# 09_Expansion_Connect.net
KiCad netlist of a schematic drawn in Altium Designer
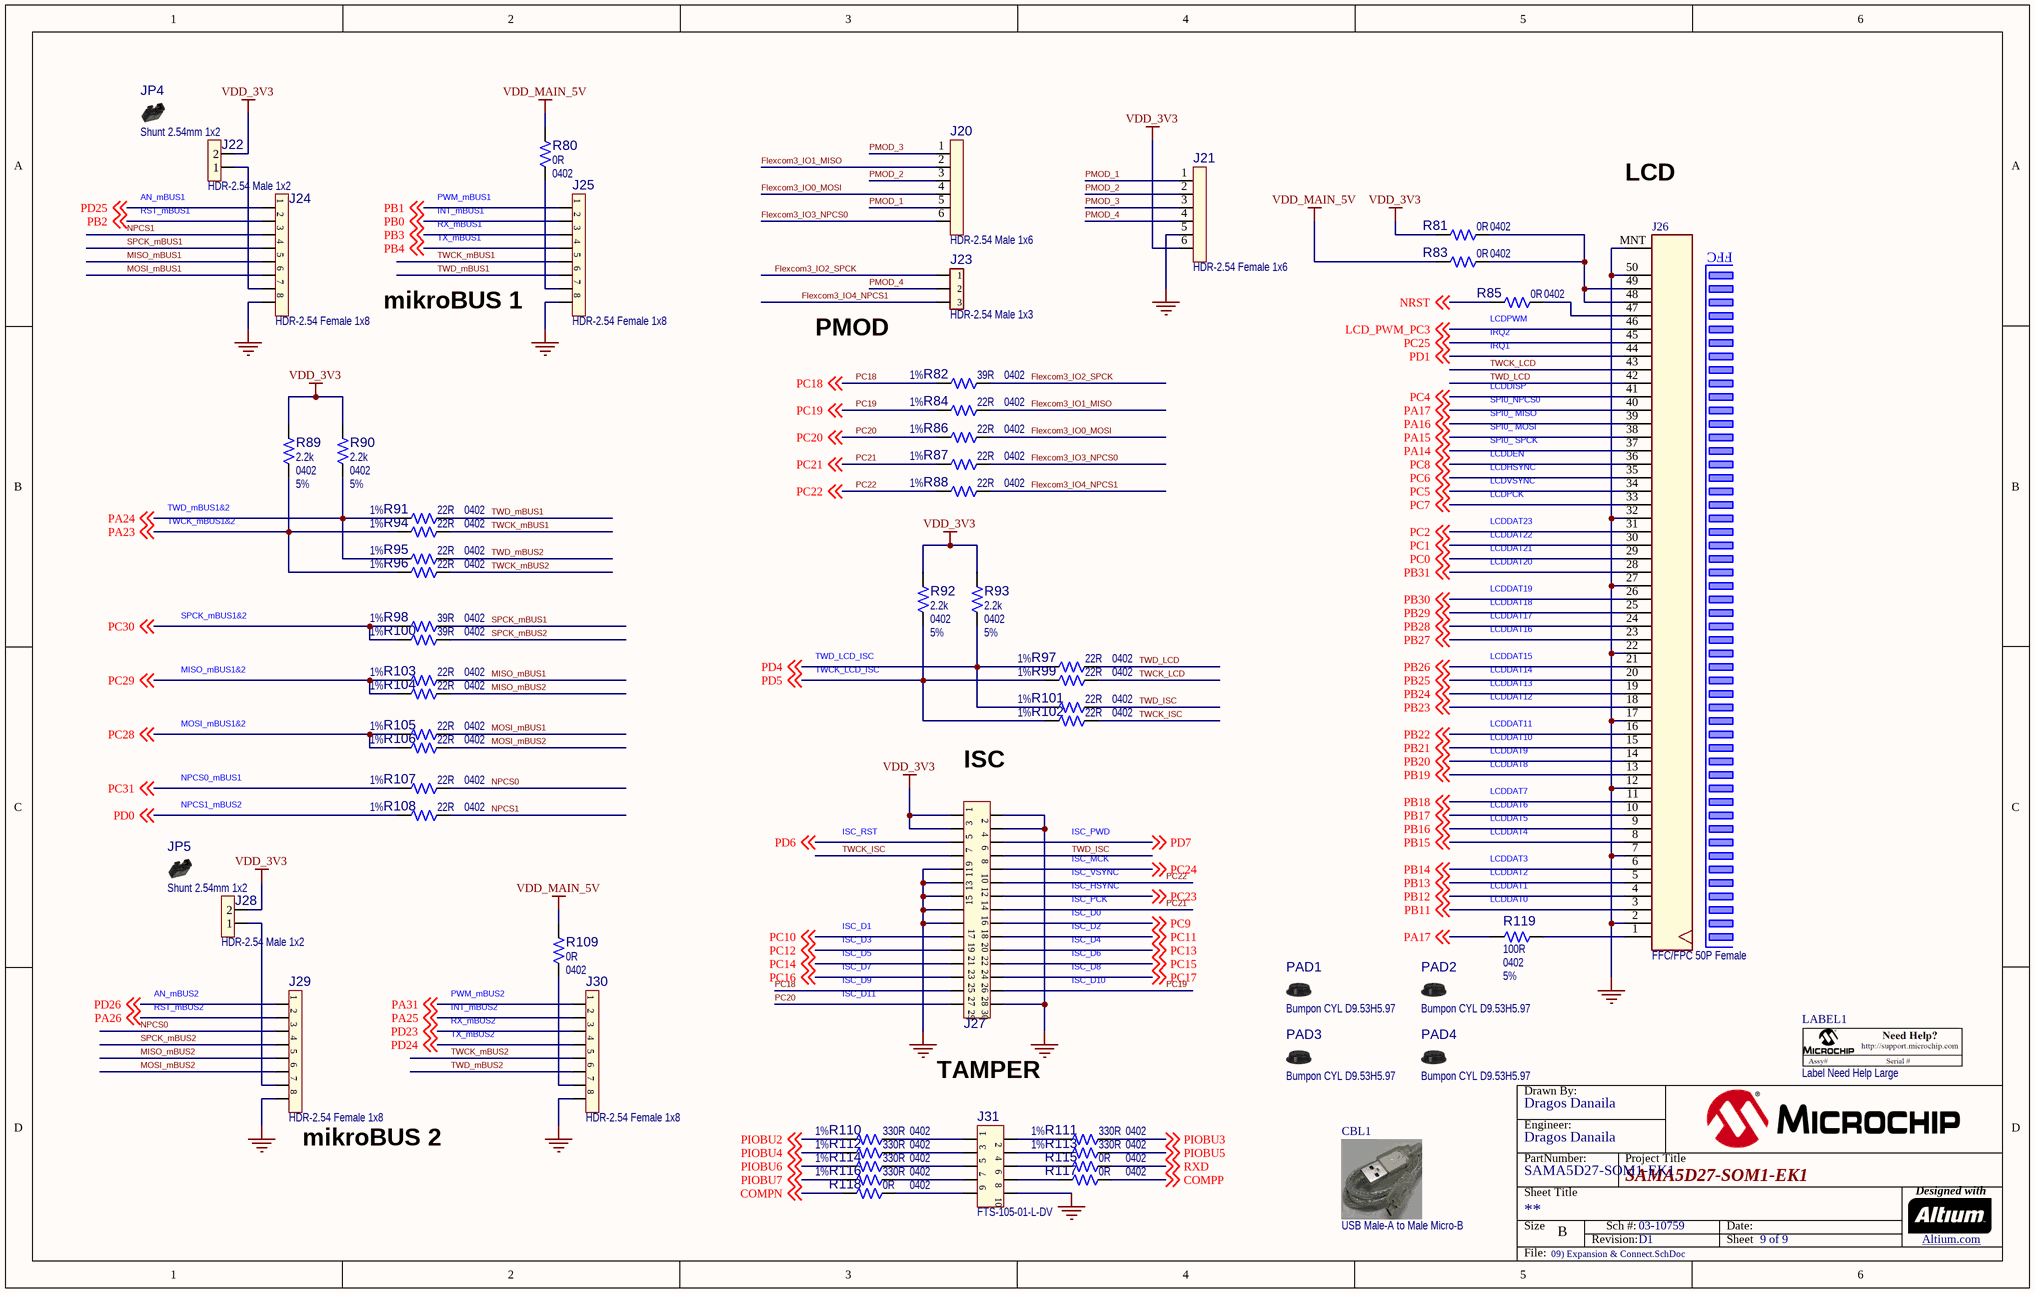
[diagram p0: 09) Expansion & Connect.SchDoc]

(export (version "E")
  (design (tool "Eeschema 10.0.6"))
  (components
    (comp (ref "CBL1")
      (value "USB Male-A to Male Micro-B")
      (fields (field (name "Comment") "Cable USB A to Micro-B"))
      (libsource (lib "MCHP-CDB") (part "Cable USB A to Micro-B"))
    )
    (comp (ref "J20")
      (value "HDR-2.54 Male 1x6")
      (footprint "HDR_M_2.54_1x6")
      (fields (field (name "Comment") "Header 1x6") (field (name "OWNER") "Bogdan P (M91398)"))
      (libsource (lib "MCHP-CDB") (part "Header 1x6"))
    )
    (comp (ref "J21")
      (value "HDR-2.54 Female 1x6")
      (footprint "HDR_F_2.54_1x6_RA")
      (fields (field (name "Comment") "Header 1x6"))
      (libsource (lib "MCHP-CDB") (part "Header 1x6"))
    )
    (comp (ref "J22")
      (value "HDR-2.54 Male 1x2")
      (footprint "HDR_M_2.54_1x2")
      (fields (field (name "Comment") "Header 1x2") (field (name "OWNER") "Bogdan P (M91398)"))
      (libsource (lib "MCHP-CDB") (part "Header 1x2"))
    )
    (comp (ref "J23")
      (value "HDR-2.54 Male 1x3")
      (footprint "HDR_M_2.54_1x3")
      (fields (field (name "Comment") "Header 1x3") (field (name "OWNER") "Bogdan P (M91398)"))
      (libsource (lib "MCHP-CDB") (part "Header 1x3"))
    )
    (comp (ref "J24")
      (value "HDR-2.54 Female 1x8")
      (footprint "HDR_F_2.54_1X8")
      (description "CON HDR-2.54 Female 1x8 Gold TH")
      (fields (field (name "Comment") "Header 1x8") (field (name "OWNER") "Jamus Griego"))
      (libsource (lib "MCHP-CDB") (part "Header 1x8"))
    )
    (comp (ref "J25")
      (value "HDR-2.54 Female 1x8")
      (footprint "HDR_F_2.54_1X8")
      (description "CON HDR-2.54 Female 1x8 Gold TH")
      (fields (field (name "Comment") "Header 1x8") (field (name "OWNER") "Jamus Griego"))
      (libsource (lib "MCHP-CDB") (part "Header 1x8"))
    )
    (comp (ref "J26")
      (value "FFC/FPC 50P Female")
      (footprint "CON_FFC_0.5_FEMALE_1X50_SMD_OMR_XF2M-5015-1A")
      (fields (field (name "Comment") "CON FFC 1x50 Mount") (field (name "OWNER") "Tad Ahlvers"))
      (libsource (lib "MCHP-CDB") (part "CON FFC 1x50 Mount"))
    )
    (comp (ref "J27")
      (value "Header 2x15")
      (footprint "HDR_M_2.54_2x15")
      (fields (field (name "OWNER") "Tim Moffat"))
      (libsource (lib "MCHP-CDB") (part "Header 2x15"))
    )
    (comp (ref "J28")
      (value "HDR-2.54 Male 1x2")
      (footprint "HDR_M_2.54_1x2")
      (fields (field (name "Comment") "Header 1x2") (field (name "OWNER") "Bogdan P (M91398)"))
      (libsource (lib "MCHP-CDB") (part "Header 1x2"))
    )
    (comp (ref "J29")
      (value "HDR-2.54 Female 1x8")
      (footprint "HDR_F_2.54_1X8")
      (description "CON HDR-2.54 Female 1x8 Gold TH")
      (fields (field (name "Comment") "Header 1x8") (field (name "OWNER") "Jamus Griego"))
      (libsource (lib "MCHP-CDB") (part "Header 1x8"))
    )
    (comp (ref "J30")
      (value "HDR-2.54 Female 1x8")
      (footprint "HDR_F_2.54_1X8")
      (description "CON HDR-2.54 Female 1x8 Gold TH")
      (fields (field (name "Comment") "Header 1x8") (field (name "OWNER") "Jamus Griego"))
      (libsource (lib "MCHP-CDB") (part "Header 1x8"))
    )
    (comp (ref "J31")
      (value "FTS-105-01-L-DV")
      (footprint "HDR_M_1.27_2x5_SMD_V_SAM_FTS-105-01-L-DV")
      (fields (field (name "Comment") "Header 2x5") (field (name "OWNER") "Dragos Danaila"))
      (libsource (lib "MCHP-CDB") (part "Header 2x5"))
    )
    (comp (ref "JP4")
      (value "Shunt 2.54mm 1x2")
      (footprint "Jumper_Mechanical")
      (fields (field (name "Comment") "Jumper Mechanical") (field (name "OWNER") "Mike Ragsdale"))
      (libsource (lib "MCHP-CDB") (part "Jumper Mechanical"))
    )
    (comp (ref "JP5")
      (value "Shunt 2.54mm 1x2")
      (footprint "Jumper_Mechanical")
      (fields (field (name "Comment") "Jumper Mechanical") (field (name "OWNER") "Mike Ragsdale"))
      (libsource (lib "MCHP-CDB") (part "Jumper Mechanical"))
    )
    (comp (ref "LABEL1")
      (value "Label Need Help Large")
      (footprint "LABEL_Need_Help_Large")
      (fields (field (name "Comment") "LABEL_Need_Help_Large"))
      (libsource (lib "MCHP-CDB") (part "LABEL_Need_Help_Large"))
    )
    (comp (ref "PAD1")
      (value "Bumpon CYL D9.53H5.97")
      (footprint "BUMP_3M_SJ61A2_CYLINDRICAL_BLACK_D9.53H5.97")
      (fields (field (name "Comment") "Rubber Pad Cylindrical") (field (name "OWNER") "Mark Loper"))
      (libsource (lib "MCHP-CDB") (part "Rubber Pad Cylindrical"))
    )
    (comp (ref "PAD2")
      (value "Bumpon CYL D9.53H5.97")
      (footprint "BUMP_3M_SJ61A2_CYLINDRICAL_BLACK_D9.53H5.97")
      (fields (field (name "Comment") "Rubber Pad Cylindrical") (field (name "OWNER") "Mark Loper"))
      (libsource (lib "MCHP-CDB") (part "Rubber Pad Cylindrical"))
    )
    (comp (ref "PAD3")
      (value "Bumpon CYL D9.53H5.97")
      (footprint "BUMP_3M_SJ61A2_CYLINDRICAL_BLACK_D9.53H5.97")
      (fields (field (name "Comment") "Rubber Pad Cylindrical") (field (name "OWNER") "Mark Loper"))
      (libsource (lib "MCHP-CDB") (part "Rubber Pad Cylindrical"))
    )
    (comp (ref "PAD4")
      (value "Bumpon CYL D9.53H5.97")
      (footprint "BUMP_3M_SJ61A2_CYLINDRICAL_BLACK_D9.53H5.97")
      (fields (field (name "Comment") "Rubber Pad Cylindrical") (field (name "OWNER") "Mark Loper"))
      (libsource (lib "MCHP-CDB") (part "Rubber Pad Cylindrical"))
    )
    (comp (ref "R80")
      (value "0R")
      (footprint "RES_C_0402")
      (description "Resistor")
      (fields (field (name "PACKAGE") "0402") (field (name "POWER") "1/10W"))
      (libsource (lib "MCHP-CDB") (part "Resistor"))
    )
    (comp (ref "R81")
      (value "0R")
      (footprint "RES_C_0402")
      (description "Resistor")
      (fields (field (name "PACKAGE") "0402") (field (name "POWER") "1/10W"))
      (libsource (lib "MCHP-CDB") (part "Resistor"))
    )
    (comp (ref "R82")
      (value "39R")
      (footprint "RES_C_0402")
      (description "Resistor")
      (fields
        (field (name "PACKAGE") "0402")
        (field (name "TOLERANCE") "1%")
        (field (name "POWER") "1/16W")
        (field (name "OWNER") "Sompoch Loboonlert")
      )
      (libsource (lib "MCHP-CDB") (part "Resistor"))
    )
    (comp (ref "R83")
      (value "0R")
      (footprint "RES_C_0402")
      (description "Resistor")
      (fields (field (name "PACKAGE") "0402") (field (name "POWER") "1/10W"))
      (libsource (lib "MCHP-CDB") (part "Resistor"))
    )
    (comp (ref "R84")
      (value "22R")
      (footprint "RES_C_0402")
      (description "Resistor")
      (fields
        (field (name "PACKAGE") "0402")
        (field (name "TOLERANCE") "1%")
        (field (name "POWER") "1/10W")
        (field (name "OWNER") "Mike Ragsdale")
      )
      (libsource (lib "MCHP-CDB") (part "Resistor"))
    )
    (comp (ref "R85")
      (value "0R")
      (footprint "RES_C_0402")
      (description "Resistor")
      (fields (field (name "PACKAGE") "0402") (field (name "POWER") "1/10W"))
      (libsource (lib "MCHP-CDB") (part "Resistor"))
    )
    (comp (ref "R86")
      (value "22R")
      (footprint "RES_C_0402")
      (description "Resistor")
      (fields
        (field (name "PACKAGE") "0402")
        (field (name "TOLERANCE") "1%")
        (field (name "POWER") "1/10W")
        (field (name "OWNER") "Mike Ragsdale")
      )
      (libsource (lib "MCHP-CDB") (part "Resistor"))
    )
    (comp (ref "R87")
      (value "22R")
      (footprint "RES_C_0402")
      (description "Resistor")
      (fields
        (field (name "PACKAGE") "0402")
        (field (name "TOLERANCE") "1%")
        (field (name "POWER") "1/10W")
        (field (name "OWNER") "Mike Ragsdale")
      )
      (libsource (lib "MCHP-CDB") (part "Resistor"))
    )
    (comp (ref "R88")
      (value "22R")
      (footprint "RES_C_0402")
      (description "Resistor")
      (fields
        (field (name "PACKAGE") "0402")
        (field (name "TOLERANCE") "1%")
        (field (name "POWER") "1/10W")
        (field (name "OWNER") "Mike Ragsdale")
      )
      (libsource (lib "MCHP-CDB") (part "Resistor"))
    )
    (comp (ref "R89")
      (value "2.2k")
      (footprint "RES_C_0402")
      (description "Resistor")
      (fields
        (field (name "PACKAGE") "0402")
        (field (name "TOLERANCE") "5%")
        (field (name "VOLTAGE") "50V")
        (field (name "POWER") "1/16W")
        (field (name "OWNER") "Tad Ahlvers")
      )
      (libsource (lib "MCHP-CDB") (part "Resistor"))
    )
    (comp (ref "R90")
      (value "2.2k")
      (footprint "RES_C_0402")
      (description "Resistor")
      (fields
        (field (name "PACKAGE") "0402")
        (field (name "TOLERANCE") "5%")
        (field (name "VOLTAGE") "50V")
        (field (name "POWER") "1/16W")
        (field (name "OWNER") "Tad Ahlvers")
      )
      (libsource (lib "MCHP-CDB") (part "Resistor"))
    )
    (comp (ref "R91")
      (value "22R")
      (footprint "RES_C_0402")
      (description "Resistor")
      (fields
        (field (name "PACKAGE") "0402")
        (field (name "TOLERANCE") "1%")
        (field (name "POWER") "1/10W")
        (field (name "OWNER") "Mike Ragsdale")
      )
      (libsource (lib "MCHP-CDB") (part "Resistor"))
    )
    (comp (ref "R92")
      (value "2.2k")
      (footprint "RES_C_0402")
      (description "Resistor")
      (fields
        (field (name "PACKAGE") "0402")
        (field (name "TOLERANCE") "5%")
        (field (name "VOLTAGE") "50V")
        (field (name "POWER") "1/16W")
        (field (name "OWNER") "Tad Ahlvers")
      )
      (libsource (lib "MCHP-CDB") (part "Resistor"))
    )
    (comp (ref "R93")
      (value "2.2k")
      (footprint "RES_C_0402")
      (description "Resistor")
      (fields
        (field (name "PACKAGE") "0402")
        (field (name "TOLERANCE") "5%")
        (field (name "VOLTAGE") "50V")
        (field (name "POWER") "1/16W")
        (field (name "OWNER") "Tad Ahlvers")
      )
      (libsource (lib "MCHP-CDB") (part "Resistor"))
    )
    (comp (ref "R94")
      (value "22R")
      (footprint "RES_C_0402")
      (description "Resistor")
      (fields
        (field (name "PACKAGE") "0402")
        (field (name "TOLERANCE") "1%")
        (field (name "POWER") "1/10W")
        (field (name "OWNER") "Mike Ragsdale")
      )
      (libsource (lib "MCHP-CDB") (part "Resistor"))
    )
    (comp (ref "R95")
      (value "22R")
      (footprint "RES_C_0402")
      (description "Resistor")
      (fields
        (field (name "PACKAGE") "0402")
        (field (name "TOLERANCE") "1%")
        (field (name "POWER") "1/10W")
        (field (name "OWNER") "Mike Ragsdale")
      )
      (libsource (lib "MCHP-CDB") (part "Resistor"))
    )
    (comp (ref "R96")
      (value "22R")
      (footprint "RES_C_0402")
      (description "Resistor")
      (fields
        (field (name "PACKAGE") "0402")
        (field (name "TOLERANCE") "1%")
        (field (name "POWER") "1/10W")
        (field (name "OWNER") "Mike Ragsdale")
      )
      (libsource (lib "MCHP-CDB") (part "Resistor"))
    )
    (comp (ref "R97")
      (value "22R")
      (footprint "RES_C_0402")
      (description "Resistor")
      (fields
        (field (name "PACKAGE") "0402")
        (field (name "TOLERANCE") "1%")
        (field (name "POWER") "1/10W")
        (field (name "OWNER") "Mike Ragsdale")
      )
      (libsource (lib "MCHP-CDB") (part "Resistor"))
    )
    (comp (ref "R98")
      (value "39R")
      (footprint "RES_C_0402")
      (description "Resistor")
      (fields
        (field (name "PACKAGE") "0402")
        (field (name "TOLERANCE") "1%")
        (field (name "POWER") "1/16W")
        (field (name "OWNER") "Sompoch Loboonlert")
      )
      (libsource (lib "MCHP-CDB") (part "Resistor"))
    )
    (comp (ref "R99")
      (value "22R")
      (footprint "RES_C_0402")
      (description "Resistor")
      (fields
        (field (name "PACKAGE") "0402")
        (field (name "TOLERANCE") "1%")
        (field (name "POWER") "1/10W")
        (field (name "OWNER") "Mike Ragsdale")
      )
      (libsource (lib "MCHP-CDB") (part "Resistor"))
    )
    (comp (ref "R100")
      (value "39R")
      (footprint "RES_C_0402")
      (description "Resistor")
      (fields
        (field (name "PACKAGE") "0402")
        (field (name "TOLERANCE") "1%")
        (field (name "POWER") "1/16W")
        (field (name "OWNER") "Sompoch Loboonlert")
      )
      (libsource (lib "MCHP-CDB") (part "Resistor"))
    )
    (comp (ref "R101")
      (value "22R")
      (footprint "RES_C_0402")
      (description "Resistor")
      (fields
        (field (name "PACKAGE") "0402")
        (field (name "TOLERANCE") "1%")
        (field (name "POWER") "1/10W")
        (field (name "OWNER") "Mike Ragsdale")
      )
      (libsource (lib "MCHP-CDB") (part "Resistor"))
    )
    (comp (ref "R102")
      (value "22R")
      (footprint "RES_C_0402")
      (description "Resistor")
      (fields
        (field (name "PACKAGE") "0402")
        (field (name "TOLERANCE") "1%")
        (field (name "POWER") "1/10W")
        (field (name "OWNER") "Mike Ragsdale")
      )
      (libsource (lib "MCHP-CDB") (part "Resistor"))
    )
    (comp (ref "R103")
      (value "22R")
      (footprint "RES_C_0402")
      (description "Resistor")
      (fields
        (field (name "PACKAGE") "0402")
        (field (name "TOLERANCE") "1%")
        (field (name "POWER") "1/10W")
        (field (name "OWNER") "Mike Ragsdale")
      )
      (libsource (lib "MCHP-CDB") (part "Resistor"))
    )
    (comp (ref "R104")
      (value "22R")
      (footprint "RES_C_0402")
      (description "Resistor")
      (fields
        (field (name "PACKAGE") "0402")
        (field (name "TOLERANCE") "1%")
        (field (name "POWER") "1/10W")
        (field (name "OWNER") "Mike Ragsdale")
      )
      (libsource (lib "MCHP-CDB") (part "Resistor"))
    )
    (comp (ref "R105")
      (value "22R")
      (footprint "RES_C_0402")
      (description "Resistor")
      (fields
        (field (name "PACKAGE") "0402")
        (field (name "TOLERANCE") "1%")
        (field (name "POWER") "1/10W")
        (field (name "OWNER") "Mike Ragsdale")
      )
      (libsource (lib "MCHP-CDB") (part "Resistor"))
    )
    (comp (ref "R106")
      (value "22R")
      (footprint "RES_C_0402")
      (description "Resistor")
      (fields
        (field (name "PACKAGE") "0402")
        (field (name "TOLERANCE") "1%")
        (field (name "POWER") "1/10W")
        (field (name "OWNER") "Mike Ragsdale")
      )
      (libsource (lib "MCHP-CDB") (part "Resistor"))
    )
    (comp (ref "R107")
      (value "22R")
      (footprint "RES_C_0402")
      (description "Resistor")
      (fields
        (field (name "PACKAGE") "0402")
        (field (name "TOLERANCE") "1%")
        (field (name "POWER") "1/10W")
        (field (name "OWNER") "Mike Ragsdale")
      )
      (libsource (lib "MCHP-CDB") (part "Resistor"))
    )
    (comp (ref "R108")
      (value "22R")
      (footprint "RES_C_0402")
      (description "Resistor")
      (fields
        (field (name "PACKAGE") "0402")
        (field (name "TOLERANCE") "1%")
        (field (name "POWER") "1/10W")
        (field (name "OWNER") "Mike Ragsdale")
      )
      (libsource (lib "MCHP-CDB") (part "Resistor"))
    )
    (comp (ref "R109")
      (value "0R")
      (footprint "RES_C_0402")
      (description "Resistor")
      (fields (field (name "PACKAGE") "0402") (field (name "POWER") "1/10W"))
      (libsource (lib "MCHP-CDB") (part "Resistor"))
    )
    (comp (ref "R110")
      (value "330R")
      (footprint "RES_C_0402")
      (description "Resistor")
      (fields
        (field (name "PACKAGE") "0402")
        (field (name "TOLERANCE") "1%")
        (field (name "POWER") "1/10W")
        (field (name "OWNER") "Stephen Humberd")
      )
      (libsource (lib "MCHP-CDB") (part "Resistor"))
    )
    (comp (ref "R111")
      (value "330R")
      (footprint "RES_C_0402")
      (description "Resistor")
      (fields
        (field (name "PACKAGE") "0402")
        (field (name "TOLERANCE") "1%")
        (field (name "POWER") "1/10W")
        (field (name "OWNER") "Stephen Humberd")
      )
      (libsource (lib "MCHP-CDB") (part "Resistor"))
    )
    (comp (ref "R112")
      (value "330R")
      (footprint "RES_C_0402")
      (description "Resistor")
      (fields
        (field (name "PACKAGE") "0402")
        (field (name "TOLERANCE") "1%")
        (field (name "POWER") "1/10W")
        (field (name "OWNER") "Stephen Humberd")
      )
      (libsource (lib "MCHP-CDB") (part "Resistor"))
    )
    (comp (ref "R113")
      (value "330R")
      (footprint "RES_C_0402")
      (description "Resistor")
      (fields
        (field (name "PACKAGE") "0402")
        (field (name "TOLERANCE") "1%")
        (field (name "POWER") "1/10W")
        (field (name "OWNER") "Stephen Humberd")
      )
      (libsource (lib "MCHP-CDB") (part "Resistor"))
    )
    (comp (ref "R114")
      (value "330R")
      (footprint "RES_C_0402")
      (description "Resistor")
      (fields
        (field (name "PACKAGE") "0402")
        (field (name "TOLERANCE") "1%")
        (field (name "POWER") "1/10W")
        (field (name "OWNER") "Stephen Humberd")
      )
      (libsource (lib "MCHP-CDB") (part "Resistor"))
    )
    (comp (ref "R115")
      (value "0R")
      (footprint "RES_C_0402")
      (description "Resistor")
      (fields (field (name "PACKAGE") "0402") (field (name "POWER") "1/10W"))
      (libsource (lib "MCHP-CDB") (part "Resistor"))
    )
    (comp (ref "R116")
      (value "330R")
      (footprint "RES_C_0402")
      (description "Resistor")
      (fields
        (field (name "PACKAGE") "0402")
        (field (name "TOLERANCE") "1%")
        (field (name "POWER") "1/10W")
        (field (name "OWNER") "Stephen Humberd")
      )
      (libsource (lib "MCHP-CDB") (part "Resistor"))
    )
    (comp (ref "R117")
      (value "0R")
      (footprint "RES_C_0402")
      (description "Resistor")
      (fields (field (name "PACKAGE") "0402") (field (name "POWER") "1/10W"))
      (libsource (lib "MCHP-CDB") (part "Resistor"))
    )
    (comp (ref "R118")
      (value "0R")
      (footprint "RES_C_0402")
      (description "Resistor")
      (fields (field (name "PACKAGE") "0402") (field (name "POWER") "1/10W"))
      (libsource (lib "MCHP-CDB") (part "Resistor"))
    )
    (comp (ref "R119")
      (value "100R")
      (footprint "RES_C_0402")
      (description "Resistor")
      (fields
        (field (name "PACKAGE") "0402")
        (field (name "TOLERANCE") "5%")
        (field (name "VOLTAGE") "50V")
        (field (name "POWER") "1/16W")
        (field (name "OWNER") "Sompoch Loboonlert")
      )
      (libsource (lib "MCHP-CDB") (part "Resistor"))
    )
  )
  (nets
    (net (code "1") (name "/Flexcom3_IO0_MOSI") (class "Default")
      (node (ref "J20") (pin "4") (pinfunction "4_4") (pintype "passive"))
      (node (ref "R86") (pin "2") (pinfunction "2_2") (pintype "passive"))
    )
    (net (code "2") (name "/Flexcom3_IO1_MISO") (class "Default")
      (node (ref "J20") (pin "2") (pinfunction "2_2") (pintype "passive"))
      (node (ref "R84") (pin "2") (pinfunction "2_2") (pintype "passive"))
    )
    (net (code "3") (name "/Flexcom3_IO2_SPCK") (class "Default")
      (node (ref "J23") (pin "1") (pinfunction "1_1") (pintype "passive"))
      (node (ref "R82") (pin "2") (pinfunction "2_2") (pintype "passive"))
    )
    (net (code "4") (name "/Flexcom3_IO3_NPCS0") (class "Default")
      (node (ref "J20") (pin "6") (pinfunction "6_6") (pintype "passive"))
      (node (ref "R87") (pin "2") (pinfunction "2_2") (pintype "passive"))
    )
    (net (code "5") (name "/Flexcom3_IO4_NPCS1") (class "Default")
      (node (ref "J23") (pin "3") (pinfunction "3_3") (pintype "passive"))
      (node (ref "R88") (pin "2") (pinfunction "2_2") (pintype "passive"))
    )
    (net (code "6") (name "/MISO_mBUS1") (class "Default")
      (node (ref "J24") (pin "5") (pinfunction "5_5") (pintype "passive"))
      (node (ref "R103") (pin "2") (pinfunction "2_2") (pintype "passive"))
    )
    (net (code "7") (name "/MISO_mBUS2") (class "Default")
      (node (ref "J29") (pin "5") (pinfunction "5_5") (pintype "passive"))
      (node (ref "R104") (pin "2") (pinfunction "2_2") (pintype "passive"))
    )
    (net (code "8") (name "/MOSI_mBUS1") (class "Default")
      (node (ref "J24") (pin "6") (pinfunction "6_6") (pintype "passive"))
      (node (ref "R105") (pin "2") (pinfunction "2_2") (pintype "passive"))
    )
    (net (code "9") (name "/MOSI_mBUS2") (class "Default")
      (node (ref "J29") (pin "6") (pinfunction "6_6") (pintype "passive"))
      (node (ref "R106") (pin "2") (pinfunction "2_2") (pintype "passive"))
    )
    (net (code "10") (name "/NPCS0") (class "Default")
      (node (ref "J29") (pin "3") (pinfunction "3_3") (pintype "passive"))
      (node (ref "R107") (pin "2") (pinfunction "2_2") (pintype "passive"))
    )
    (net (code "11") (name "/NPCS1") (class "Default")
      (node (ref "J24") (pin "3") (pinfunction "3_3") (pintype "passive"))
      (node (ref "R108") (pin "2") (pinfunction "2_2") (pintype "passive"))
    )
    (net (code "12") (name "/PMOD_1") (class "Default")
      (node (ref "J20") (pin "5") (pinfunction "5_5") (pintype "passive"))
      (node (ref "J21") (pin "1") (pinfunction "1_1") (pintype "passive"))
    )
    (net (code "13") (name "/PMOD_2") (class "Default")
      (node (ref "J20") (pin "3") (pinfunction "3_3") (pintype "passive"))
      (node (ref "J21") (pin "2") (pinfunction "2_2") (pintype "passive"))
    )
    (net (code "14") (name "/PMOD_3") (class "Default")
      (node (ref "J20") (pin "1") (pinfunction "1_1") (pintype "passive"))
      (node (ref "J21") (pin "3") (pinfunction "3_3") (pintype "passive"))
    )
    (net (code "15") (name "/PMOD_4") (class "Default")
      (node (ref "J21") (pin "4") (pinfunction "4_4") (pintype "passive"))
      (node (ref "J23") (pin "2") (pinfunction "2_2") (pintype "passive"))
    )
    (net (code "16") (name "/SPCK_mBUS1") (class "Default")
      (node (ref "J24") (pin "4") (pinfunction "4_4") (pintype "passive"))
      (node (ref "R98") (pin "2") (pinfunction "2_2") (pintype "passive"))
    )
    (net (code "17") (name "/SPCK_mBUS2") (class "Default")
      (node (ref "J29") (pin "4") (pinfunction "4_4") (pintype "passive"))
      (node (ref "R100") (pin "2") (pinfunction "2_2") (pintype "passive"))
    )
    (net (code "18") (name "/TWCK_ISC") (class "Default")
      (node (ref "J27") (pin "7") (pinfunction "7_7") (pintype "passive"))
      (node (ref "R102") (pin "2") (pinfunction "2_2") (pintype "passive"))
    )
    (net (code "19") (name "/TWCK_LCD") (class "Default")
      (node (ref "J26") (pin "43") (pinfunction "43_43") (pintype "passive"))
      (node (ref "R99") (pin "2") (pinfunction "2_2") (pintype "passive"))
    )
    (net (code "20") (name "/TWCK_mBUS1") (class "Default")
      (node (ref "J25") (pin "5") (pinfunction "5_5") (pintype "passive"))
      (node (ref "R94") (pin "2") (pinfunction "2_2") (pintype "passive"))
    )
    (net (code "21") (name "/TWCK_mBUS2") (class "Default")
      (node (ref "J30") (pin "5") (pinfunction "5_5") (pintype "passive"))
      (node (ref "R96") (pin "2") (pinfunction "2_2") (pintype "passive"))
    )
    (net (code "22") (name "/TWD_ISC") (class "Default")
      (node (ref "J27") (pin "8") (pinfunction "8_8") (pintype "passive"))
      (node (ref "R101") (pin "2") (pinfunction "2_2") (pintype "passive"))
    )
    (net (code "23") (name "/TWD_LCD") (class "Default")
      (node (ref "J26") (pin "42") (pinfunction "42_42") (pintype "passive"))
      (node (ref "R97") (pin "2") (pinfunction "2_2") (pintype "passive"))
    )
    (net (code "24") (name "/TWD_mBUS1") (class "Default")
      (node (ref "J25") (pin "6") (pinfunction "6_6") (pintype "passive"))
      (node (ref "R91") (pin "2") (pinfunction "2_2") (pintype "passive"))
    )
    (net (code "25") (name "/TWD_mBUS2") (class "Default")
      (node (ref "J30") (pin "6") (pinfunction "6_6") (pintype "passive"))
      (node (ref "R95") (pin "2") (pinfunction "2_2") (pintype "passive"))
    )
    (net (code "26") (name "COMPN") (class "Default")
      (node (ref "R118") (pin "1") (pinfunction "1_1") (pintype "passive"))
    )
    (net (code "27") (name "COMPP") (class "Default")
      (node (ref "R117") (pin "2") (pinfunction "2_2") (pintype "passive"))
    )
    (net (code "28") (name "GND_POWER") (class "Default")
      (node (ref "J21") (pin "5") (pinfunction "5_5") (pintype "passive"))
      (node (ref "J24") (pin "8") (pinfunction "8_8") (pintype "passive"))
      (node (ref "J25") (pin "8") (pinfunction "8_8") (pintype "passive"))
      (node (ref "J26") (pin "12") (pinfunction "12_12") (pintype "passive"))
      (node (ref "J26") (pin "17") (pinfunction "17_17") (pintype "passive"))
      (node (ref "J26") (pin "2") (pinfunction "2_2") (pintype "passive"))
      (node (ref "J26") (pin "22") (pinfunction "22_22") (pintype "passive"))
      (node (ref "J26") (pin "27") (pinfunction "27_27") (pintype "passive"))
      (node (ref "J26") (pin "32") (pinfunction "32_32") (pintype "passive"))
      (node (ref "J26") (pin "50") (pinfunction "50_50") (pintype "passive"))
      (node (ref "J26") (pin "7") (pinfunction "7_7") (pintype "passive"))
      (node (ref "J26") (pin "MNT") (pinfunction "MNT_MNT") (pintype "passive"))
      (node (ref "J27") (pin "11") (pinfunction "11_11") (pintype "passive"))
      (node (ref "J27") (pin "13") (pinfunction "13_13") (pintype "passive"))
      (node (ref "J27") (pin "15") (pinfunction "15_15") (pintype "passive"))
      (node (ref "J27") (pin "17") (pinfunction "17_17") (pintype "passive"))
      (node (ref "J27") (pin "2") (pinfunction "2_2") (pintype "passive"))
      (node (ref "J27") (pin "30") (pinfunction "30_30") (pintype "passive"))
      (node (ref "J27") (pin "4") (pinfunction "4_4") (pintype "passive"))
      (node (ref "J27") (pin "9") (pinfunction "9_9") (pintype "passive"))
      (node (ref "J29") (pin "8") (pinfunction "8_8") (pintype "passive"))
      (node (ref "J30") (pin "8") (pinfunction "8_8") (pintype "passive"))
      (node (ref "J31") (pin "10") (pinfunction "10_10") (pintype "passive"))
    )
    (net (code "29") (name "LCD_PWM_PC3") (class "Default")
      (node (ref "J26") (pin "46") (pinfunction "46_46") (pintype "passive"))
    )
    (net (code "30") (name "NRST") (class "Default")
      (node (ref "R85") (pin "1") (pinfunction "1_1") (pintype "passive"))
    )
    (net (code "31") (name "Net-(J22-Pad1)") (class "Default")
      (node (ref "J22") (pin "1") (pinfunction "1_1") (pintype "passive"))
      (node (ref "J24") (pin "7") (pinfunction "7_7") (pintype "passive"))
    )
    (net (code "32") (name "Net-(J25-Pad7)") (class "Default")
      (node (ref "J25") (pin "7") (pinfunction "7_7") (pintype "passive"))
      (node (ref "R80") (pin "1") (pinfunction "1_1") (pintype "passive"))
    )
    (net (code "33") (name "Net-(J26-Pad1)") (class "Default")
      (node (ref "J26") (pin "1") (pinfunction "1_1") (pintype "passive"))
      (node (ref "R119") (pin "2") (pinfunction "2_2") (pintype "passive"))
    )
    (net (code "34") (name "Net-(J26-Pad47)") (class "Default")
      (node (ref "J26") (pin "47") (pinfunction "47_47") (pintype "passive"))
      (node (ref "R85") (pin "2") (pinfunction "2_2") (pintype "passive"))
    )
    (net (code "35") (name "Net-(J26-Pad48)") (class "Default")
      (node (ref "J26") (pin "48") (pinfunction "48_48") (pintype "passive"))
      (node (ref "J26") (pin "49") (pinfunction "49_49") (pintype "passive"))
      (node (ref "R81") (pin "2") (pinfunction "2_2") (pintype "passive"))
      (node (ref "R83") (pin "2") (pinfunction "2_2") (pintype "passive"))
    )
    (net (code "36") (name "Net-(J28-Pad1)") (class "Default")
      (node (ref "J28") (pin "1") (pinfunction "1_1") (pintype "passive"))
      (node (ref "J29") (pin "7") (pinfunction "7_7") (pintype "passive"))
    )
    (net (code "37") (name "Net-(J30-Pad7)") (class "Default")
      (node (ref "J30") (pin "7") (pinfunction "7_7") (pintype "passive"))
      (node (ref "R109") (pin "1") (pinfunction "1_1") (pintype "passive"))
    )
    (net (code "38") (name "Net-(J31-Pad1)") (class "Default")
      (node (ref "J31") (pin "1") (pinfunction "1_1") (pintype "passive"))
      (node (ref "R110") (pin "2") (pinfunction "2_2") (pintype "passive"))
    )
    (net (code "39") (name "Net-(J31-Pad2)") (class "Default")
      (node (ref "J31") (pin "2") (pinfunction "2_2") (pintype "passive"))
      (node (ref "R111") (pin "1") (pinfunction "1_1") (pintype "passive"))
    )
    (net (code "40") (name "Net-(J31-Pad3)") (class "Default")
      (node (ref "J31") (pin "3") (pinfunction "3_3") (pintype "passive"))
      (node (ref "R112") (pin "2") (pinfunction "2_2") (pintype "passive"))
    )
    (net (code "41") (name "Net-(J31-Pad4)") (class "Default")
      (node (ref "J31") (pin "4") (pinfunction "4_4") (pintype "passive"))
      (node (ref "R113") (pin "1") (pinfunction "1_1") (pintype "passive"))
    )
    (net (code "42") (name "Net-(J31-Pad5)") (class "Default")
      (node (ref "J31") (pin "5") (pinfunction "5_5") (pintype "passive"))
      (node (ref "R114") (pin "2") (pinfunction "2_2") (pintype "passive"))
    )
    (net (code "43") (name "Net-(J31-Pad6)") (class "Default")
      (node (ref "J31") (pin "6") (pinfunction "6_6") (pintype "passive"))
      (node (ref "R115") (pin "1") (pinfunction "1_1") (pintype "passive"))
    )
    (net (code "44") (name "Net-(J31-Pad7)") (class "Default")
      (node (ref "J31") (pin "7") (pinfunction "7_7") (pintype "passive"))
      (node (ref "R116") (pin "2") (pinfunction "2_2") (pintype "passive"))
    )
    (net (code "45") (name "Net-(J31-Pad8)") (class "Default")
      (node (ref "J31") (pin "8") (pinfunction "8_8") (pintype "passive"))
      (node (ref "R117") (pin "1") (pinfunction "1_1") (pintype "passive"))
    )
    (net (code "46") (name "Net-(J31-Pad9)") (class "Default")
      (node (ref "J31") (pin "9") (pinfunction "9_9") (pintype "passive"))
      (node (ref "R118") (pin "2") (pinfunction "2_2") (pintype "passive"))
    )
    (net (code "47") (name "PA14") (class "Default")
      (node (ref "J26") (pin "37") (pinfunction "37_37") (pintype "passive"))
    )
    (net (code "48") (name "PA15") (class "Default")
      (node (ref "J26") (pin "38") (pinfunction "38_38") (pintype "passive"))
    )
    (net (code "49") (name "PA16") (class "Default")
      (node (ref "J26") (pin "39") (pinfunction "39_39") (pintype "passive"))
    )
    (net (code "50") (name "PA17") (class "Default")
      (node (ref "J26") (pin "40") (pinfunction "40_40") (pintype "passive"))
      (node (ref "R119") (pin "1") (pinfunction "1_1") (pintype "passive"))
    )
    (net (code "51") (name "PA23") (class "Default")
      (node (ref "R89") (pin "2") (pinfunction "2_2") (pintype "passive"))
      (node (ref "R94") (pin "1") (pinfunction "1_1") (pintype "passive"))
      (node (ref "R96") (pin "1") (pinfunction "1_1") (pintype "passive"))
    )
    (net (code "52") (name "PA24") (class "Default")
      (node (ref "R90") (pin "2") (pinfunction "2_2") (pintype "passive"))
      (node (ref "R91") (pin "1") (pinfunction "1_1") (pintype "passive"))
      (node (ref "R95") (pin "1") (pinfunction "1_1") (pintype "passive"))
    )
    (net (code "53") (name "PA25") (class "Default")
      (node (ref "J30") (pin "2") (pinfunction "2_2") (pintype "passive"))
    )
    (net (code "54") (name "PA26") (class "Default")
      (node (ref "J29") (pin "2") (pinfunction "2_2") (pintype "passive"))
    )
    (net (code "55") (name "PA31") (class "Default")
      (node (ref "J30") (pin "1") (pinfunction "1_1") (pintype "passive"))
    )
    (net (code "56") (name "PB0") (class "Default")
      (node (ref "J25") (pin "2") (pinfunction "2_2") (pintype "passive"))
    )
    (net (code "57") (name "PB1") (class "Default")
      (node (ref "J25") (pin "1") (pinfunction "1_1") (pintype "passive"))
    )
    (net (code "58") (name "PB2") (class "Default")
      (node (ref "J24") (pin "2") (pinfunction "2_2") (pintype "passive"))
    )
    (net (code "59") (name "PB3") (class "Default")
      (node (ref "J25") (pin "3") (pinfunction "3_3") (pintype "passive"))
    )
    (net (code "60") (name "PB4") (class "Default")
      (node (ref "J25") (pin "4") (pinfunction "4_4") (pintype "passive"))
    )
    (net (code "61") (name "PB11") (class "Default")
      (node (ref "J26") (pin "3") (pinfunction "3_3") (pintype "passive"))
    )
    (net (code "62") (name "PB12") (class "Default")
      (node (ref "J26") (pin "4") (pinfunction "4_4") (pintype "passive"))
    )
    (net (code "63") (name "PB13") (class "Default")
      (node (ref "J26") (pin "5") (pinfunction "5_5") (pintype "passive"))
    )
    (net (code "64") (name "PB14") (class "Default")
      (node (ref "J26") (pin "6") (pinfunction "6_6") (pintype "passive"))
    )
    (net (code "65") (name "PB15") (class "Default")
      (node (ref "J26") (pin "8") (pinfunction "8_8") (pintype "passive"))
    )
    (net (code "66") (name "PB16") (class "Default")
      (node (ref "J26") (pin "9") (pinfunction "9_9") (pintype "passive"))
    )
    (net (code "67") (name "PB17") (class "Default")
      (node (ref "J26") (pin "10") (pinfunction "10_10") (pintype "passive"))
    )
    (net (code "68") (name "PB18") (class "Default")
      (node (ref "J26") (pin "11") (pinfunction "11_11") (pintype "passive"))
    )
    (net (code "69") (name "PB19") (class "Default")
      (node (ref "J26") (pin "13") (pinfunction "13_13") (pintype "passive"))
    )
    (net (code "70") (name "PB20") (class "Default")
      (node (ref "J26") (pin "14") (pinfunction "14_14") (pintype "passive"))
    )
    (net (code "71") (name "PB21") (class "Default")
      (node (ref "J26") (pin "15") (pinfunction "15_15") (pintype "passive"))
    )
    (net (code "72") (name "PB22") (class "Default")
      (node (ref "J26") (pin "16") (pinfunction "16_16") (pintype "passive"))
    )
    (net (code "73") (name "PB23") (class "Default")
      (node (ref "J26") (pin "18") (pinfunction "18_18") (pintype "passive"))
    )
    (net (code "74") (name "PB24") (class "Default")
      (node (ref "J26") (pin "19") (pinfunction "19_19") (pintype "passive"))
    )
    (net (code "75") (name "PB25") (class "Default")
      (node (ref "J26") (pin "20") (pinfunction "20_20") (pintype "passive"))
    )
    (net (code "76") (name "PB26") (class "Default")
      (node (ref "J26") (pin "21") (pinfunction "21_21") (pintype "passive"))
    )
    (net (code "77") (name "PB27") (class "Default")
      (node (ref "J26") (pin "23") (pinfunction "23_23") (pintype "passive"))
    )
    (net (code "78") (name "PB28") (class "Default")
      (node (ref "J26") (pin "24") (pinfunction "24_24") (pintype "passive"))
    )
    (net (code "79") (name "PB29") (class "Default")
      (node (ref "J26") (pin "25") (pinfunction "25_25") (pintype "passive"))
    )
    (net (code "80") (name "PB30") (class "Default")
      (node (ref "J26") (pin "26") (pinfunction "26_26") (pintype "passive"))
    )
    (net (code "81") (name "PB31") (class "Default")
      (node (ref "J26") (pin "28") (pinfunction "28_28") (pintype "passive"))
    )
    (net (code "82") (name "PC0") (class "Default")
      (node (ref "J26") (pin "29") (pinfunction "29_29") (pintype "passive"))
    )
    (net (code "83") (name "PC1") (class "Default")
      (node (ref "J26") (pin "30") (pinfunction "30_30") (pintype "passive"))
    )
    (net (code "84") (name "PC2") (class "Default")
      (node (ref "J26") (pin "31") (pinfunction "31_31") (pintype "passive"))
    )
    (net (code "85") (name "PC4") (class "Default")
      (node (ref "J26") (pin "41") (pinfunction "41_41") (pintype "passive"))
    )
    (net (code "86") (name "PC5") (class "Default")
      (node (ref "J26") (pin "34") (pinfunction "34_34") (pintype "passive"))
    )
    (net (code "87") (name "PC6") (class "Default")
      (node (ref "J26") (pin "35") (pinfunction "35_35") (pintype "passive"))
    )
    (net (code "88") (name "PC7") (class "Default")
      (node (ref "J26") (pin "33") (pinfunction "33_33") (pintype "passive"))
    )
    (net (code "89") (name "PC8") (class "Default")
      (node (ref "J26") (pin "36") (pinfunction "36_36") (pintype "passive"))
    )
    (net (code "90") (name "PC9") (class "Default")
      (node (ref "J27") (pin "18") (pinfunction "18_18") (pintype "passive"))
    )
    (net (code "91") (name "PC10") (class "Default")
      (node (ref "J27") (pin "19") (pinfunction "19_19") (pintype "passive"))
    )
    (net (code "92") (name "PC11") (class "Default")
      (node (ref "J27") (pin "20") (pinfunction "20_20") (pintype "passive"))
    )
    (net (code "93") (name "PC12") (class "Default")
      (node (ref "J27") (pin "21") (pinfunction "21_21") (pintype "passive"))
    )
    (net (code "94") (name "PC13") (class "Default")
      (node (ref "J27") (pin "22") (pinfunction "22_22") (pintype "passive"))
    )
    (net (code "95") (name "PC14") (class "Default")
      (node (ref "J27") (pin "23") (pinfunction "23_23") (pintype "passive"))
    )
    (net (code "96") (name "PC15") (class "Default")
      (node (ref "J27") (pin "24") (pinfunction "24_24") (pintype "passive"))
    )
    (net (code "97") (name "PC16") (class "Default")
      (node (ref "J27") (pin "25") (pinfunction "25_25") (pintype "passive"))
    )
    (net (code "98") (name "PC17") (class "Default")
      (node (ref "J27") (pin "26") (pinfunction "26_26") (pintype "passive"))
    )
    (net (code "99") (name "PC18") (class "Default")
      (node (ref "J27") (pin "27") (pinfunction "27_27") (pintype "passive"))
      (node (ref "R82") (pin "1") (pinfunction "1_1") (pintype "passive"))
    )
    (net (code "100") (name "PC19") (class "Default")
      (node (ref "J27") (pin "28") (pinfunction "28_28") (pintype "passive"))
      (node (ref "R84") (pin "1") (pinfunction "1_1") (pintype "passive"))
    )
    (net (code "101") (name "PC20") (class "Default")
      (node (ref "J27") (pin "29") (pinfunction "29_29") (pintype "passive"))
      (node (ref "R86") (pin "1") (pinfunction "1_1") (pintype "passive"))
    )
    (net (code "102") (name "PC21") (class "Default")
      (node (ref "J27") (pin "16") (pinfunction "16_16") (pintype "passive"))
      (node (ref "R87") (pin "1") (pinfunction "1_1") (pintype "passive"))
    )
    (net (code "103") (name "PC22") (class "Default")
      (node (ref "J27") (pin "12") (pinfunction "12_12") (pintype "passive"))
      (node (ref "R88") (pin "1") (pinfunction "1_1") (pintype "passive"))
    )
    (net (code "104") (name "PC23") (class "Default")
      (node (ref "J27") (pin "14") (pinfunction "14_14") (pintype "passive"))
    )
    (net (code "105") (name "PC24") (class "Default")
      (node (ref "J27") (pin "10") (pinfunction "10_10") (pintype "passive"))
    )
    (net (code "106") (name "PC25") (class "Default")
      (node (ref "J26") (pin "45") (pinfunction "45_45") (pintype "passive"))
    )
    (net (code "107") (name "PC28") (class "Default")
      (node (ref "R105") (pin "1") (pinfunction "1_1") (pintype "passive"))
      (node (ref "R106") (pin "1") (pinfunction "1_1") (pintype "passive"))
    )
    (net (code "108") (name "PC29") (class "Default")
      (node (ref "R103") (pin "1") (pinfunction "1_1") (pintype "passive"))
      (node (ref "R104") (pin "1") (pinfunction "1_1") (pintype "passive"))
    )
    (net (code "109") (name "PC30") (class "Default")
      (node (ref "R100") (pin "1") (pinfunction "1_1") (pintype "passive"))
      (node (ref "R98") (pin "1") (pinfunction "1_1") (pintype "passive"))
    )
    (net (code "110") (name "PC31") (class "Default")
      (node (ref "R107") (pin "1") (pinfunction "1_1") (pintype "passive"))
    )
    (net (code "111") (name "PD0") (class "Default")
      (node (ref "R108") (pin "1") (pinfunction "1_1") (pintype "passive"))
    )
    (net (code "112") (name "PD1") (class "Default")
      (node (ref "J26") (pin "44") (pinfunction "44_44") (pintype "passive"))
    )
    (net (code "113") (name "PD4") (class "Default")
      (node (ref "R101") (pin "1") (pinfunction "1_1") (pintype "passive"))
      (node (ref "R93") (pin "2") (pinfunction "2_2") (pintype "passive"))
      (node (ref "R97") (pin "1") (pinfunction "1_1") (pintype "passive"))
    )
    (net (code "114") (name "PD5") (class "Default")
      (node (ref "R102") (pin "1") (pinfunction "1_1") (pintype "passive"))
      (node (ref "R92") (pin "2") (pinfunction "2_2") (pintype "passive"))
      (node (ref "R99") (pin "1") (pinfunction "1_1") (pintype "passive"))
    )
    (net (code "115") (name "PD6") (class "Default")
      (node (ref "J27") (pin "5") (pinfunction "5_5") (pintype "passive"))
    )
    (net (code "116") (name "PD7") (class "Default")
      (node (ref "J27") (pin "6") (pinfunction "6_6") (pintype "passive"))
    )
    (net (code "117") (name "PD23") (class "Default")
      (node (ref "J30") (pin "3") (pinfunction "3_3") (pintype "passive"))
    )
    (net (code "118") (name "PD24") (class "Default")
      (node (ref "J30") (pin "4") (pinfunction "4_4") (pintype "passive"))
    )
    (net (code "119") (name "PD25") (class "Default")
      (node (ref "J24") (pin "1") (pinfunction "1_1") (pintype "passive"))
    )
    (net (code "120") (name "PD26") (class "Default")
      (node (ref "J29") (pin "1") (pinfunction "1_1") (pintype "passive"))
    )
    (net (code "121") (name "PIOBU2") (class "Default")
      (node (ref "R110") (pin "1") (pinfunction "1_1") (pintype "passive"))
    )
    (net (code "122") (name "PIOBU3") (class "Default")
      (node (ref "R111") (pin "2") (pinfunction "2_2") (pintype "passive"))
    )
    (net (code "123") (name "PIOBU4") (class "Default")
      (node (ref "R112") (pin "1") (pinfunction "1_1") (pintype "passive"))
    )
    (net (code "124") (name "PIOBU5") (class "Default")
      (node (ref "R113") (pin "2") (pinfunction "2_2") (pintype "passive"))
    )
    (net (code "125") (name "PIOBU6") (class "Default")
      (node (ref "R114") (pin "1") (pinfunction "1_1") (pintype "passive"))
    )
    (net (code "126") (name "PIOBU7") (class "Default")
      (node (ref "R116") (pin "1") (pinfunction "1_1") (pintype "passive"))
    )
    (net (code "127") (name "RXD") (class "Default")
      (node (ref "R115") (pin "2") (pinfunction "2_2") (pintype "passive"))
    )
    (net (code "128") (name "VDD_3V3") (class "Default")
      (node (ref "J21") (pin "6") (pinfunction "6_6") (pintype "passive"))
      (node (ref "J22") (pin "2") (pinfunction "2_2") (pintype "passive"))
      (node (ref "J27") (pin "1") (pinfunction "1_1") (pintype "passive"))
      (node (ref "J27") (pin "3") (pinfunction "3_3") (pintype "passive"))
      (node (ref "J28") (pin "2") (pinfunction "2_2") (pintype "passive"))
      (node (ref "R81") (pin "1") (pinfunction "1_1") (pintype "passive"))
      (node (ref "R89") (pin "1") (pinfunction "1_1") (pintype "passive"))
      (node (ref "R90") (pin "1") (pinfunction "1_1") (pintype "passive"))
      (node (ref "R92") (pin "1") (pinfunction "1_1") (pintype "passive"))
      (node (ref "R93") (pin "1") (pinfunction "1_1") (pintype "passive"))
    )
    (net (code "129") (name "VDD_MAIN_5V") (class "Default")
      (node (ref "R109") (pin "2") (pinfunction "2_2") (pintype "passive"))
      (node (ref "R80") (pin "2") (pinfunction "2_2") (pintype "passive"))
      (node (ref "R83") (pin "1") (pinfunction "1_1") (pintype "passive"))
    )
  )
)
